# RADIO.net
KiCad netlist of a schematic drawn in Altium Designer
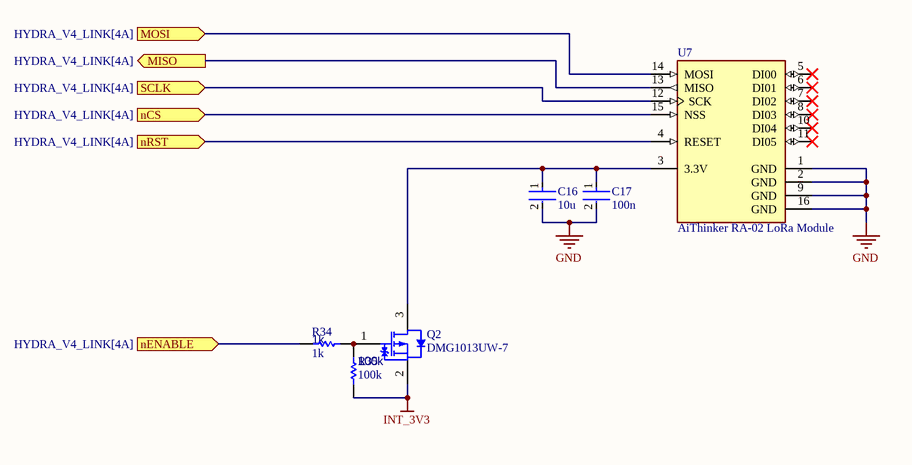
[diagram p0: RADIO.SchDoc]

(export (version "E")
  (design (tool "Eeschema 10.0.6"))
  (components
    (comp (ref "C16")
      (value "10u")
      (footprint "FP-0402-L_1_0_0_05-W_0_5-IPC_A")
      (description "LARGE PADS, 0402 CAP, CHANGE COMMENT TO MATCH REAL P/N")
      (libsource (lib "Space Concordia") (part "b4654b650e69147ec39a6b967a45e02"))
    )
    (comp (ref "C17")
      (value "100n")
      (footprint "FP-0402-L_1_0_0_05-W_0_5-IPC_A")
      (description "LARGE PADS, 0402 CAP, CHANGE COMMENT TO MATCH REAL P/N")
      (libsource (lib "Space Concordia") (part "b4654b650e69147ec39a6b967a45e02"))
    )
    (comp (ref "Q2")
      (value "DMG1013UW-7")
      (footprint "DIOD-SOT323-3_V")
      (fields (field (name "MANUFACTURER") "Diodes Inc"))
      (libsource (lib "Altium Content Vault") (part "PEMOS-GSD-3_C"))
    )
    (comp (ref "R34")
      (value "1k")
      (footprint "R0603B")
      (description "Resistor")
      (fields (field (name "ALTIUM_VALUE") "1k"))
      (libsource (lib "Space Concordia") (part "Resistor"))
    )
    (comp (ref "R35")
      (value "100k")
      (footprint "R0603B")
      (description "Resistor")
      (fields (field (name "ALTIUM_VALUE") "100k"))
      (libsource (lib "Space Concordia") (part "Resistor"))
    )
    (comp (ref "U7")
      (value "AiThinker RA-02 LoRa Module")
      (footprint "AiThinker RA-02 LoRa Module-Footprint-1")
      (libsource (lib "Space Concordia") (part "AiThinker RA-02"))
    )
  )
  (nets
    (net (code "1") (name "/MISO") (class "Default")
      (node (ref "U7") (pin "13") (pinfunction "MISO_13") (pintype "output"))
    )
    (net (code "2") (name "/MOSI") (class "Default")
      (node (ref "U7") (pin "14") (pinfunction "MOSI_14") (pintype "input"))
    )
    (net (code "3") (name "/SCLK") (class "Default")
      (node (ref "U7") (pin "12") (pinfunction "SCK_12") (pintype "input"))
    )
    (net (code "4") (name "/nCS") (class "Default")
      (node (ref "U7") (pin "15") (pinfunction "NSS_15") (pintype "input"))
    )
    (net (code "5") (name "/nENABLE") (class "Default")
      (node (ref "R34") (pin "1") (pinfunction "1_1") (pintype "passive"))
    )
    (net (code "6") (name "/nRST") (class "Default")
      (node (ref "U7") (pin "4") (pinfunction "RESET_4") (pintype "input"))
    )
    (net (code "7") (name "GND") (class "Default")
      (node (ref "C16") (pin "2") (pinfunction "2_2") (pintype "passive"))
      (node (ref "C17") (pin "2") (pinfunction "2_2") (pintype "passive"))
      (node (ref "U7") (pin "1") (pinfunction "GND_1") (pintype "power_in"))
      (node (ref "U7") (pin "16") (pinfunction "GND_16") (pintype "power_in"))
      (node (ref "U7") (pin "2") (pinfunction "GND_2") (pintype "power_in"))
      (node (ref "U7") (pin "9") (pinfunction "GND_9") (pintype "power_in"))
    )
    (net (code "8") (name "INT_3V3") (class "Default")
      (node (ref "Q2") (pin "2") (pinfunction "S_2") (pintype "passive"))
      (node (ref "R35") (pin "2") (pinfunction "2_2") (pintype "passive"))
    )
    (net (code "9") (name "Net-(Q2-D)") (class "Default")
      (node (ref "C16") (pin "1") (pinfunction "1_1") (pintype "passive"))
      (node (ref "C17") (pin "1") (pinfunction "1_1") (pintype "passive"))
      (node (ref "Q2") (pin "3") (pinfunction "D_3") (pintype "passive"))
      (node (ref "U7") (pin "3") (pinfunction "3.3V_3") (pintype "power_in"))
    )
    (net (code "10") (name "Net-(Q2-G)") (class "Default")
      (node (ref "Q2") (pin "1") (pinfunction "G_1") (pintype "passive"))
      (node (ref "R34") (pin "2") (pinfunction "2_2") (pintype "passive"))
      (node (ref "R35") (pin "1") (pinfunction "1_1") (pintype "passive"))
    )
    (net (code "11") (name "unconnected-(U7-DI00-Pad5)") (class "Default")
      (node (ref "U7") (pin "5") (pinfunction "DI00_5") (pintype "bidirectional+no_connect"))
    )
    (net (code "12") (name "unconnected-(U7-DI01-Pad6)") (class "Default")
      (node (ref "U7") (pin "6") (pinfunction "DI01_6") (pintype "bidirectional+no_connect"))
    )
    (net (code "13") (name "unconnected-(U7-DI02-Pad7)") (class "Default")
      (node (ref "U7") (pin "7") (pinfunction "DI02_7") (pintype "bidirectional+no_connect"))
    )
    (net (code "14") (name "unconnected-(U7-DI03-Pad8)") (class "Default")
      (node (ref "U7") (pin "8") (pinfunction "DI03_8") (pintype "bidirectional+no_connect"))
    )
    (net (code "15") (name "unconnected-(U7-DI04-Pad10)") (class "Default")
      (node (ref "U7") (pin "10") (pinfunction "DI04_10") (pintype "bidirectional+no_connect"))
    )
    (net (code "16") (name "unconnected-(U7-DI05-Pad11)") (class "Default")
      (node (ref "U7") (pin "11") (pinfunction "DI05_11") (pintype "bidirectional+no_connect"))
    )
  )
)
